# adapter.net
KiCad netlist of a schematic drawn in EAGLE
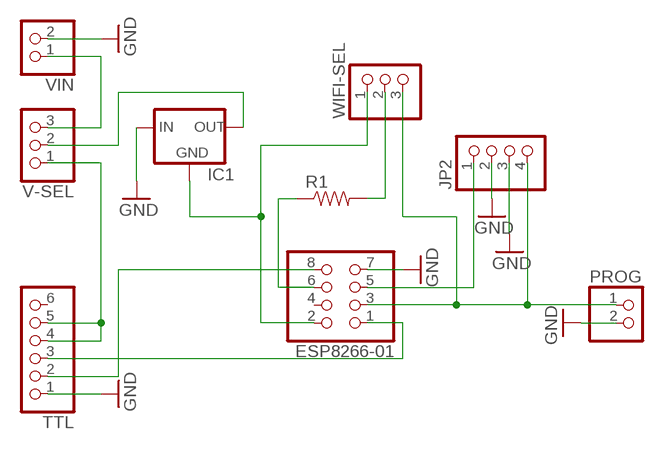
[diagram p0: schematic, sheet 1]

(export (version "E")
  (design (tool "Eeschema 10.0.6"))
  (components
    (comp (ref "ESP8266-01")
      (value "PINHD-2X4")
      (footprint "eagle-import:2X04")
      (libsource (lib "eagle-import") (part "PINHD-2X4"))
    )
    (comp (ref "IC1")
      (value "V_REG_78XXSIDE")
      (footprint "eagle-import:78XXL")
      (libsource (lib "eagle-import") (part "V_REG_78XXSIDE"))
    )
    (comp (ref "JP2")
      (value "PINHD-1X4")
      (footprint "eagle-import:1X04")
      (libsource (lib "eagle-import") (part "PINHD-1X4"))
    )
    (comp (ref "PROG")
      (value "PINHD-1X2")
      (footprint "eagle-import:1X02")
      (libsource (lib "eagle-import") (part "PINHD-1X2"))
    )
    (comp (ref "R1")
      (value "RESISTORAXIAL-0.3")
      (footprint "eagle-import:AXIAL-0.3")
      (libsource (lib "eagle-import") (part "RESISTORAXIAL-0.3"))
    )
    (comp (ref "TTL")
      (value "PINHD-1X6")
      (footprint "eagle-import:1X06")
      (libsource (lib "eagle-import") (part "PINHD-1X6"))
    )
    (comp (ref "V-SEL")
      (value "PINHD-1X3")
      (footprint "eagle-import:1X03")
      (libsource (lib "eagle-import") (part "PINHD-1X3"))
    )
    (comp (ref "VIN")
      (value "PINHD-1X2")
      (footprint "eagle-import:1X02")
      (libsource (lib "eagle-import") (part "PINHD-1X2"))
    )
    (comp (ref "WIFI-SEL")
      (value "PINHD-1X3")
      (footprint "eagle-import:1X03")
      (libsource (lib "eagle-import") (part "PINHD-1X3"))
    )
  )
  (nets
    (net (code "1") (name "GND") (class "Default")
      (node (ref "ESP8266-01") (pin "7") (pinfunction "7_7") (pintype "passive"))
      (node (ref "IC1") (pin "IN") (pinfunction "IN_IN") (pintype "input"))
      (node (ref "JP2") (pin "2") (pinfunction "2_2") (pintype "passive"))
      (node (ref "JP2") (pin "3") (pinfunction "3_3") (pintype "passive"))
      (node (ref "PROG") (pin "2") (pinfunction "2_2") (pintype "passive"))
      (node (ref "TTL") (pin "1") (pinfunction "1_1") (pintype "passive"))
      (node (ref "VIN") (pin "2") (pinfunction "2_2") (pintype "passive"))
    )
    (net (code "2") (name "Net-(ESP8266-01-Pad1)") (class "Default")
      (node (ref "ESP8266-01") (pin "1") (pinfunction "1_1") (pintype "passive"))
      (node (ref "TTL") (pin "3") (pinfunction "3_3") (pintype "passive"))
    )
    (net (code "3") (name "Net-(ESP8266-01-Pad2)") (class "Default")
      (node (ref "ESP8266-01") (pin "2") (pinfunction "2_2") (pintype "passive"))
      (node (ref "IC1") (pin "GND") (pinfunction "GND_GND") (pintype "input"))
      (node (ref "WIFI-SEL") (pin "1") (pinfunction "1_1") (pintype "passive"))
    )
    (net (code "4") (name "Net-(ESP8266-01-Pad3)") (class "Default")
      (node (ref "ESP8266-01") (pin "3") (pinfunction "3_3") (pintype "passive"))
      (node (ref "JP2") (pin "4") (pinfunction "4_4") (pintype "passive"))
      (node (ref "PROG") (pin "1") (pinfunction "1_1") (pintype "passive"))
      (node (ref "WIFI-SEL") (pin "3") (pinfunction "3_3") (pintype "passive"))
    )
    (net (code "5") (name "Net-(ESP8266-01-Pad5)") (class "Default")
      (node (ref "ESP8266-01") (pin "5") (pinfunction "5_5") (pintype "passive"))
      (node (ref "JP2") (pin "1") (pinfunction "1_1") (pintype "passive"))
    )
    (net (code "6") (name "Net-(ESP8266-01-Pad8)") (class "Default")
      (node (ref "ESP8266-01") (pin "8") (pinfunction "8_8") (pintype "passive"))
      (node (ref "TTL") (pin "2") (pinfunction "2_2") (pintype "passive"))
    )
    (net (code "7") (name "Net-(IC1-PadOUT)") (class "Default")
      (node (ref "IC1") (pin "OUT") (pinfunction "OUT_OUT") (pintype "output"))
      (node (ref "V-SEL") (pin "2") (pinfunction "2_2") (pintype "passive"))
    )
    (net (code "8") (name "Net-(R1-1)") (class "Default")
      (node (ref "ESP8266-01") (pin "6") (pinfunction "6_6") (pintype "passive"))
      (node (ref "R1") (pin "P$1") (pinfunction "1_P$1") (pintype "passive"))
    )
    (net (code "9") (name "Net-(R1-2)") (class "Default")
      (node (ref "R1") (pin "P$2") (pinfunction "2_P$2") (pintype "passive"))
      (node (ref "WIFI-SEL") (pin "2") (pinfunction "2_2") (pintype "passive"))
    )
    (net (code "10") (name "Net-(TTL-Pad4)") (class "Default")
      (node (ref "TTL") (pin "4") (pinfunction "4_4") (pintype "passive"))
      (node (ref "TTL") (pin "5") (pinfunction "5_5") (pintype "passive"))
      (node (ref "V-SEL") (pin "1") (pinfunction "1_1") (pintype "passive"))
    )
    (net (code "11") (name "Net-(V-SEL-Pad3)") (class "Default")
      (node (ref "V-SEL") (pin "3") (pinfunction "3_3") (pintype "passive"))
      (node (ref "VIN") (pin "1") (pinfunction "1_1") (pintype "passive"))
    )
    (net (code "12") (name "unconnected-(ESP8266-01-Pad4)") (class "Default")
      (node (ref "ESP8266-01") (pin "4") (pinfunction "4_4") (pintype "passive"))
    )
    (net (code "13") (name "unconnected-(TTL-Pad6)") (class "Default")
      (node (ref "TTL") (pin "6") (pinfunction "6_6") (pintype "passive"))
    )
  )
)
